# MotorEncoders.net
KiCad netlist of a schematic drawn in Altium Designer
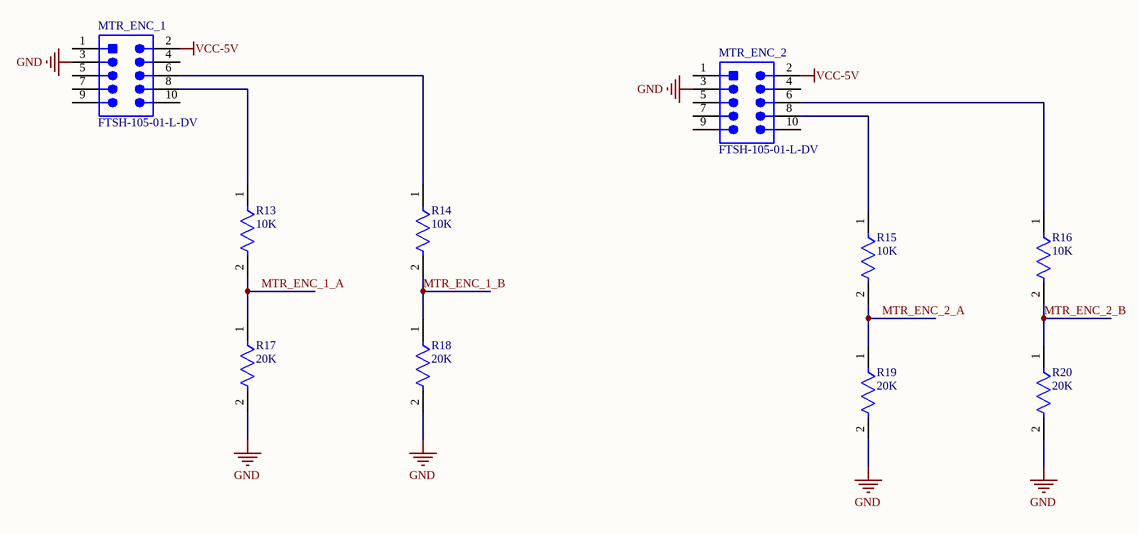
[diagram p0: MotorEncoders.SchDoc]

(export (version "E")
  (design (tool "Eeschema 10.0.6"))
  (components
    (comp (ref "MTR_ENC_1")
      (value "FTSH-105-01-L-DV")
      (footprint "SMTC-FTSH-105-01-L-DV_V")
      (description "Male Header, Pitch 1.27 mm, 2 x 5 Position, Height 5.96 mm, -55 to 125 degC, RoHS, Bulk")
      (fields (field (name "MANUFACTURER") "Samtec"))
      (libsource (lib "Altium Content Vault") (part "CN-2P-M-R10"))
    )
    (comp (ref "MTR_ENC_2")
      (value "FTSH-105-01-L-DV")
      (footprint "SMTC-FTSH-105-01-L-DV_V")
      (description "Male Header, Pitch 1.27 mm, 2 x 5 Position, Height 5.96 mm, -55 to 125 degC, RoHS, Bulk")
      (fields (field (name "MANUFACTURER") "Samtec"))
      (libsource (lib "Altium Content Vault") (part "CN-2P-M-R10"))
    )
    (comp (ref "R13")
      (value "10K")
      (footprint "FP-RC0603-0_55-IPC_C")
      (description "RES 10K OHM 1% 1/10W 0603")
      (fields (field (name "TOLERANCE") "1%"))
      (libsource (lib "Altium Content Vault") (part "1029c3af85768c4190bb7ad29bc67b5"))
    )
    (comp (ref "R14")
      (value "10K")
      (footprint "FP-RC0603-0_55-IPC_C")
      (description "RES 10K OHM 1% 1/10W 0603")
      (fields (field (name "TOLERANCE") "1%"))
      (libsource (lib "Altium Content Vault") (part "1029c3af85768c4190bb7ad29bc67b5"))
    )
    (comp (ref "R15")
      (value "10K")
      (footprint "FP-RC0603-0_55-IPC_C")
      (description "RES 10K OHM 1% 1/10W 0603")
      (fields (field (name "TOLERANCE") "1%"))
      (libsource (lib "Altium Content Vault") (part "1029c3af85768c4190bb7ad29bc67b5"))
    )
    (comp (ref "R16")
      (value "10K")
      (footprint "FP-RC0603-0_55-IPC_C")
      (description "RES 10K OHM 1% 1/10W 0603")
      (fields (field (name "TOLERANCE") "1%"))
      (libsource (lib "Altium Content Vault") (part "1029c3af85768c4190bb7ad29bc67b5"))
    )
    (comp (ref "R17")
      (value "20K")
      (footprint "FP-RC0603-0_55-IPC_C")
      (description "RES 20K OHM 1% 1/10W 0603")
      (fields (field (name "TOLERANCE") "1%"))
      (libsource (lib "Altium Content Vault") (part "1029c3af85768c4190bb7ad29bc67b5"))
    )
    (comp (ref "R18")
      (value "20K")
      (footprint "FP-RC0603-0_55-IPC_C")
      (description "RES 20K OHM 1% 1/10W 0603")
      (fields (field (name "TOLERANCE") "1%"))
      (libsource (lib "Altium Content Vault") (part "1029c3af85768c4190bb7ad29bc67b5"))
    )
    (comp (ref "R19")
      (value "20K")
      (footprint "FP-RC0603-0_55-IPC_C")
      (description "RES 20K OHM 1% 1/10W 0603")
      (fields (field (name "TOLERANCE") "1%"))
      (libsource (lib "Altium Content Vault") (part "1029c3af85768c4190bb7ad29bc67b5"))
    )
    (comp (ref "R20")
      (value "20K")
      (footprint "FP-RC0603-0_55-IPC_C")
      (description "RES 20K OHM 1% 1/10W 0603")
      (fields (field (name "TOLERANCE") "1%"))
      (libsource (lib "Altium Content Vault") (part "1029c3af85768c4190bb7ad29bc67b5"))
    )
  )
  (nets
    (net (code "1") (name "/MTR_ENC_1_A") (class "Default")
      (node (ref "R13") (pin "2") (pinfunction "2_2") (pintype "passive"))
      (node (ref "R17") (pin "1") (pinfunction "1_1") (pintype "passive"))
    )
    (net (code "2") (name "/MTR_ENC_1_B") (class "Default")
      (node (ref "R14") (pin "2") (pinfunction "2_2") (pintype "passive"))
      (node (ref "R18") (pin "1") (pinfunction "1_1") (pintype "passive"))
    )
    (net (code "3") (name "/MTR_ENC_2_A") (class "Default")
      (node (ref "R15") (pin "2") (pinfunction "2_2") (pintype "passive"))
      (node (ref "R19") (pin "1") (pinfunction "1_1") (pintype "passive"))
    )
    (net (code "4") (name "/MTR_ENC_2_B") (class "Default")
      (node (ref "R16") (pin "2") (pinfunction "2_2") (pintype "passive"))
      (node (ref "R20") (pin "1") (pinfunction "1_1") (pintype "passive"))
    )
    (net (code "5") (name "GND") (class "Default")
      (node (ref "MTR_ENC_1") (pin "3") (pinfunction "3_3") (pintype "passive"))
      (node (ref "MTR_ENC_2") (pin "3") (pinfunction "3_3") (pintype "passive"))
      (node (ref "R17") (pin "2") (pinfunction "2_2") (pintype "passive"))
      (node (ref "R18") (pin "2") (pinfunction "2_2") (pintype "passive"))
      (node (ref "R19") (pin "2") (pinfunction "2_2") (pintype "passive"))
      (node (ref "R20") (pin "2") (pinfunction "2_2") (pintype "passive"))
    )
    (net (code "6") (name "Net-(MTR_ENC_1-Pad6)") (class "Default")
      (node (ref "MTR_ENC_1") (pin "6") (pinfunction "6_6") (pintype "passive"))
      (node (ref "R14") (pin "1") (pinfunction "1_1") (pintype "passive"))
    )
    (net (code "7") (name "Net-(MTR_ENC_1-Pad8)") (class "Default")
      (node (ref "MTR_ENC_1") (pin "8") (pinfunction "8_8") (pintype "passive"))
      (node (ref "R13") (pin "1") (pinfunction "1_1") (pintype "passive"))
    )
    (net (code "8") (name "Net-(MTR_ENC_2-Pad6)") (class "Default")
      (node (ref "MTR_ENC_2") (pin "6") (pinfunction "6_6") (pintype "passive"))
      (node (ref "R16") (pin "1") (pinfunction "1_1") (pintype "passive"))
    )
    (net (code "9") (name "Net-(MTR_ENC_2-Pad8)") (class "Default")
      (node (ref "MTR_ENC_2") (pin "8") (pinfunction "8_8") (pintype "passive"))
      (node (ref "R15") (pin "1") (pinfunction "1_1") (pintype "passive"))
    )
    (net (code "10") (name "VCC-5V") (class "Default")
      (node (ref "MTR_ENC_1") (pin "2") (pinfunction "2_2") (pintype "passive"))
      (node (ref "MTR_ENC_2") (pin "2") (pinfunction "2_2") (pintype "passive"))
    )
    (net (code "11") (name "unconnected-(MTR_ENC_1-Pad1)") (class "Default")
      (node (ref "MTR_ENC_1") (pin "1") (pinfunction "1_1") (pintype "passive"))
    )
    (net (code "12") (name "unconnected-(MTR_ENC_1-Pad4)") (class "Default")
      (node (ref "MTR_ENC_1") (pin "4") (pinfunction "4_4") (pintype "passive"))
    )
    (net (code "13") (name "unconnected-(MTR_ENC_1-Pad5)") (class "Default")
      (node (ref "MTR_ENC_1") (pin "5") (pinfunction "5_5") (pintype "passive"))
    )
    (net (code "14") (name "unconnected-(MTR_ENC_1-Pad7)") (class "Default")
      (node (ref "MTR_ENC_1") (pin "7") (pinfunction "7_7") (pintype "passive"))
    )
    (net (code "15") (name "unconnected-(MTR_ENC_1-Pad9)") (class "Default")
      (node (ref "MTR_ENC_1") (pin "9") (pinfunction "9_9") (pintype "passive"))
    )
    (net (code "16") (name "unconnected-(MTR_ENC_1-Pad10)") (class "Default")
      (node (ref "MTR_ENC_1") (pin "10") (pinfunction "10_10") (pintype "passive"))
    )
    (net (code "17") (name "unconnected-(MTR_ENC_2-Pad1)") (class "Default")
      (node (ref "MTR_ENC_2") (pin "1") (pinfunction "1_1") (pintype "passive"))
    )
    (net (code "18") (name "unconnected-(MTR_ENC_2-Pad4)") (class "Default")
      (node (ref "MTR_ENC_2") (pin "4") (pinfunction "4_4") (pintype "passive"))
    )
    (net (code "19") (name "unconnected-(MTR_ENC_2-Pad5)") (class "Default")
      (node (ref "MTR_ENC_2") (pin "5") (pinfunction "5_5") (pintype "passive"))
    )
    (net (code "20") (name "unconnected-(MTR_ENC_2-Pad7)") (class "Default")
      (node (ref "MTR_ENC_2") (pin "7") (pinfunction "7_7") (pintype "passive"))
    )
    (net (code "21") (name "unconnected-(MTR_ENC_2-Pad9)") (class "Default")
      (node (ref "MTR_ENC_2") (pin "9") (pinfunction "9_9") (pintype "passive"))
    )
    (net (code "22") (name "unconnected-(MTR_ENC_2-Pad10)") (class "Default")
      (node (ref "MTR_ENC_2") (pin "10") (pinfunction "10_10") (pintype "passive"))
    )
  )
)
